# OSO-MISC-21-011_RFID.net
KiCad netlist of a schematic drawn in EAGLE
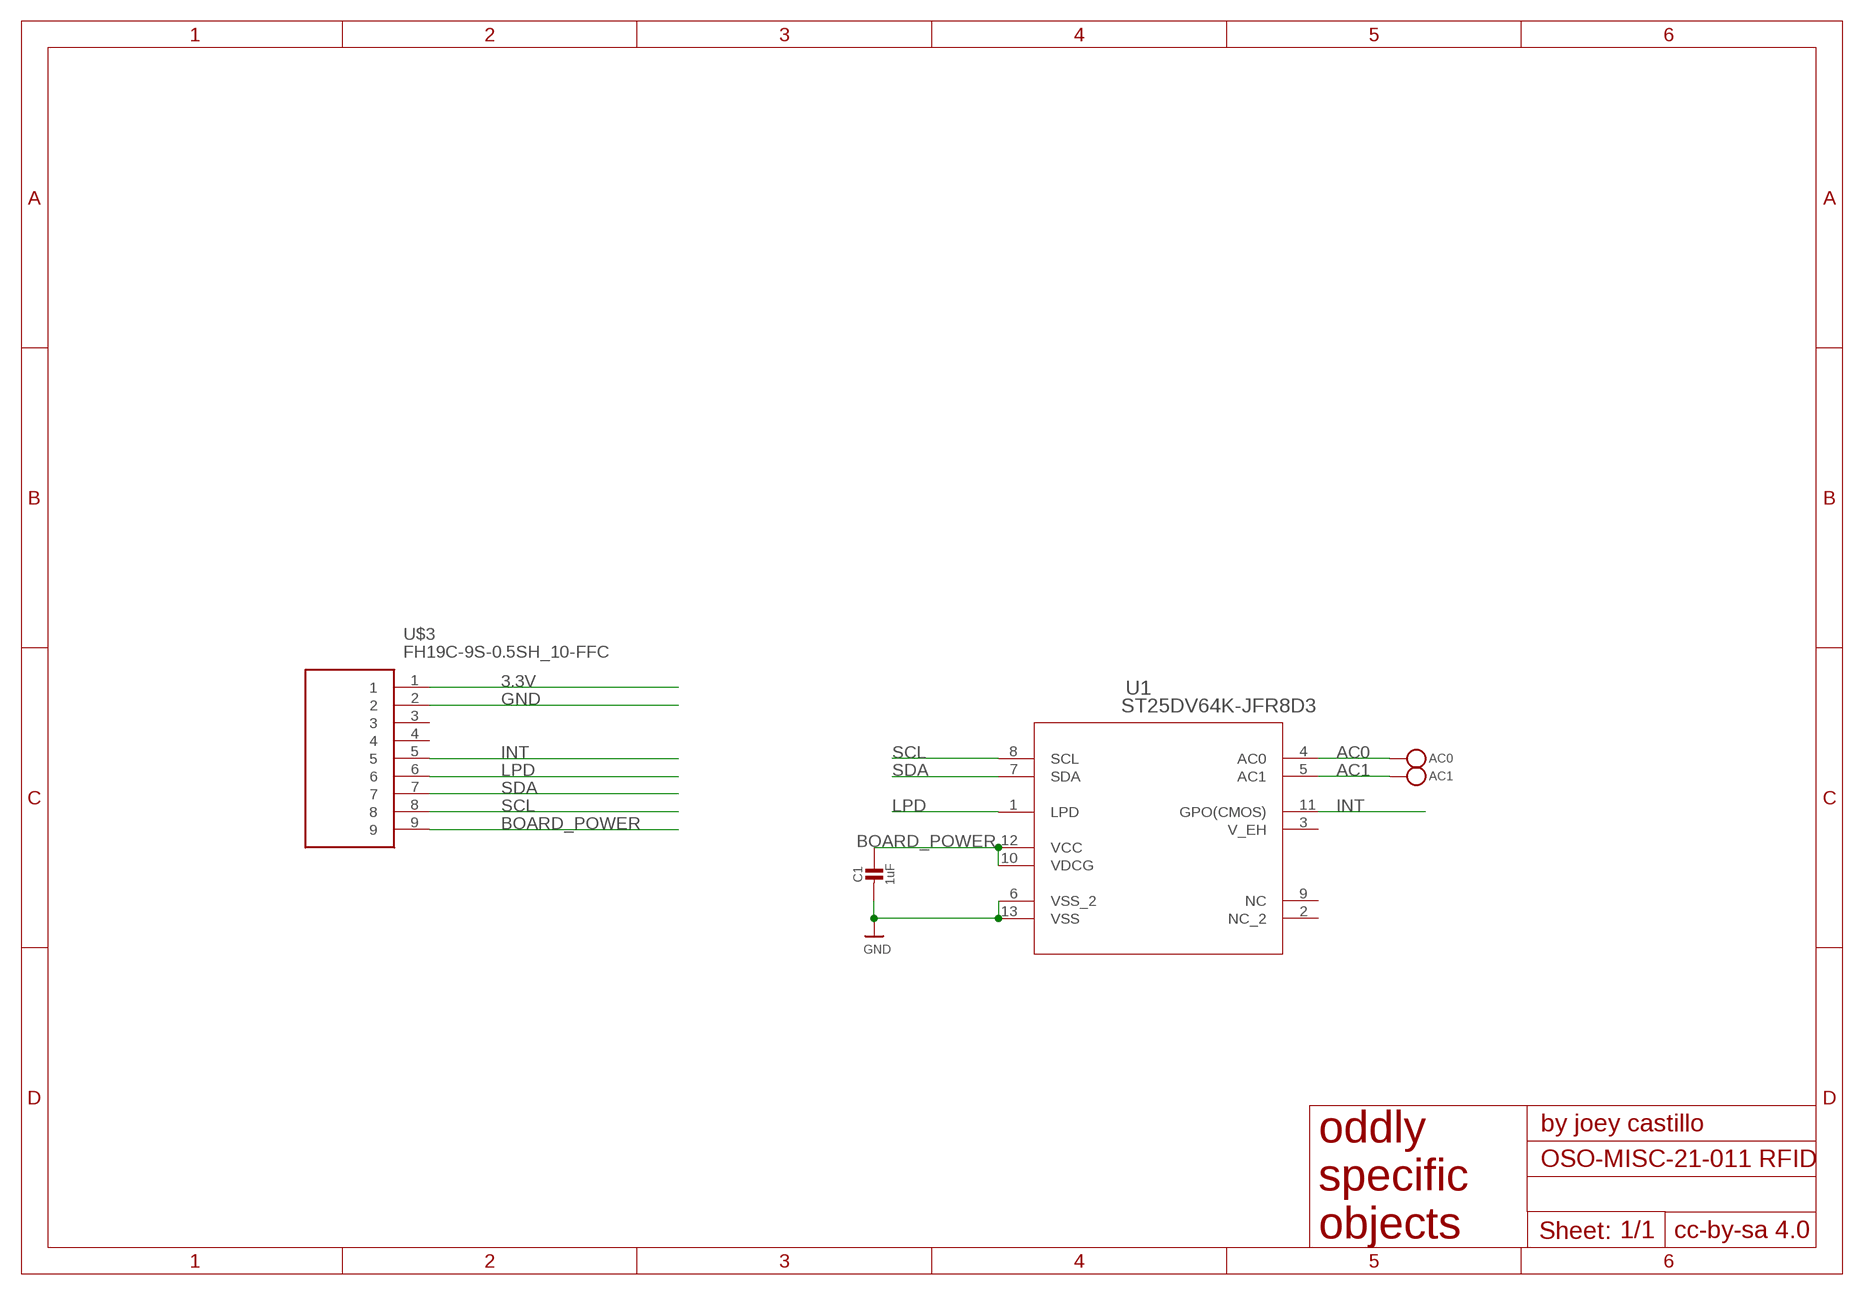
[diagram p0: schematic, sheet 1]

(export (version "E")
  (design (tool "Eeschema 10.0.6"))
  (components
    (comp (ref "AC0")
      (value "MICROBUILDER_TESTPOINT1.5X2.0MM_NOCREAM")
      (footprint "eagle-import:MICROBUILDER_PAD-1.5X2.0")
      (libsource (lib "eagle-import") (part "MICROBUILDER_TESTPOINT1.5X2.0MM_NOCREAM"))
    )
    (comp (ref "AC1")
      (value "MICROBUILDER_TESTPOINT1.5X2.0MM_NOCREAM")
      (footprint "eagle-import:MICROBUILDER_PAD-1.5X2.0")
      (libsource (lib "eagle-import") (part "MICROBUILDER_TESTPOINT1.5X2.0MM_NOCREAM"))
    )
    (comp (ref "C1")
      (value "1uF")
      (footprint "eagle-import:_0603MP")
      (libsource (lib "eagle-import") (part "CAP_CERAMIC_0603MP"))
    )
    (comp (ref "U$3")
      (value "FH19C-9S-0.5SH_10-FFC")
      (footprint "eagle-import:FH19C9S05SH10-FFC")
      (libsource (lib "eagle-import") (part "FH19C-9S-0.5SH_10-FFC"))
    )
    (comp (ref "U1")
      (value "ST25DV64K-JFR8D3")
      (footprint "eagle-import:UFDFPN12_3X3_STM")
      (fields (field (name "COPYRIGHT") "Copyright (C) 2021 Ultra Librarian. All rights reserved."))
      (libsource (lib "eagle-import") (part "ST25DV64K-JFR8D3"))
    )
  )
  (nets
    (net (code "1") (name "/3.3V") (class "Default")
      (node (ref "U$3") (pin "1") (pinfunction "1_1") (pintype "bidirectional"))
    )
    (net (code "2") (name "/AC0") (class "Default")
      (node (ref "AC0") (pin "P$1") (pinfunction "P$1_P$1") (pintype "bidirectional"))
      (node (ref "U1") (pin "4") (pinfunction "AC0_4") (pintype "bidirectional"))
    )
    (net (code "3") (name "/AC1") (class "Default")
      (node (ref "AC1") (pin "P$1") (pinfunction "P$1_P$1") (pintype "bidirectional"))
      (node (ref "U1") (pin "5") (pinfunction "AC1_5") (pintype "bidirectional"))
    )
    (net (code "4") (name "/BOARD_POWER") (class "Default")
      (node (ref "C1") (pin "1") (pinfunction "1_1") (pintype "passive"))
      (node (ref "U$3") (pin "9") (pinfunction "9_9") (pintype "bidirectional"))
      (node (ref "U1") (pin "10") (pinfunction "VDCG_10") (pintype "power_in"))
      (node (ref "U1") (pin "12") (pinfunction "VCC_12") (pintype "power_in"))
    )
    (net (code "5") (name "/INT") (class "Default")
      (node (ref "U$3") (pin "5") (pinfunction "5_5") (pintype "bidirectional"))
      (node (ref "U1") (pin "11") (pinfunction "GPO(CMOS)_11") (pintype "output"))
    )
    (net (code "6") (name "/LPD") (class "Default")
      (node (ref "U$3") (pin "6") (pinfunction "6_6") (pintype "bidirectional"))
      (node (ref "U1") (pin "1") (pinfunction "LPD_1") (pintype "input"))
    )
    (net (code "7") (name "/SCL") (class "Default")
      (node (ref "U$3") (pin "8") (pinfunction "8_8") (pintype "bidirectional"))
      (node (ref "U1") (pin "8") (pinfunction "SCL_8") (pintype "input"))
    )
    (net (code "8") (name "/SDA") (class "Default")
      (node (ref "U$3") (pin "7") (pinfunction "7_7") (pintype "bidirectional"))
      (node (ref "U1") (pin "7") (pinfunction "SDA_7") (pintype "bidirectional"))
    )
    (net (code "9") (name "GND") (class "Default")
      (node (ref "C1") (pin "2") (pinfunction "2_2") (pintype "passive"))
      (node (ref "U$3") (pin "2") (pinfunction "2_2") (pintype "bidirectional"))
      (node (ref "U1") (pin "13") (pinfunction "VSS_13") (pintype "passive"))
      (node (ref "U1") (pin "6") (pinfunction "VSS_2_6") (pintype "passive"))
    )
    (net (code "10") (name "unconnected-(U$3-Pad3)") (class "Default")
      (node (ref "U$3") (pin "3") (pinfunction "3_3") (pintype "bidirectional"))
    )
    (net (code "11") (name "unconnected-(U$3-Pad4)") (class "Default")
      (node (ref "U$3") (pin "4") (pinfunction "4_4") (pintype "bidirectional"))
    )
    (net (code "12") (name "unconnected-(U1-NC-Pad9)") (class "Default")
      (node (ref "U1") (pin "9") (pinfunction "NC_9") (pintype "no_connect"))
    )
    (net (code "13") (name "unconnected-(U1-NC_2-Pad2)") (class "Default")
      (node (ref "U1") (pin "2") (pinfunction "NC_2_2") (pintype "no_connect"))
    )
    (net (code "14") (name "unconnected-(U1-V_EH-Pad3)") (class "Default")
      (node (ref "U1") (pin "3") (pinfunction "V_EH_3") (pintype "output"))
    )
  )
)
